# line_sensor.net
KiCad netlist of a schematic drawn in EAGLE
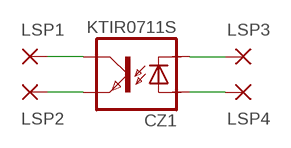
[diagram p0: schematic, sheet 1]

(export (version "E")
  (design (tool "Eeschema 10.0.6"))
  (components
    (comp (ref "CZ1")
      (value "KTIR0711S")
      (footprint "eagle-import:TOP")
      (libsource (lib "eagle-import") (part "KTIR0711S"))
    )
    (comp (ref "LSP1")
      (value "1,6/0,9")
      (footprint "eagle-import:1,6_0,9")
      (libsource (lib "eagle-import") (part "1,6/0,9"))
    )
    (comp (ref "LSP2")
      (value "1,6/0,9")
      (footprint "eagle-import:1,6_0,9")
      (libsource (lib "eagle-import") (part "1,6/0,9"))
    )
    (comp (ref "LSP3")
      (value "1,6/0,9")
      (footprint "eagle-import:1,6_0,9")
      (libsource (lib "eagle-import") (part "1,6/0,9"))
    )
    (comp (ref "LSP4")
      (value "1,6/0,9")
      (footprint "eagle-import:1,6_0,9")
      (libsource (lib "eagle-import") (part "1,6/0,9"))
    )
  )
  (nets
    (net (code "1") (name "Net-(LSP1-P)") (class "Default")
      (node (ref "CZ1") (pin "KOLEKTOR") (pinfunction "KOLEKTOR_KOLEKTOR") (pintype "bidirectional"))
      (node (ref "LSP1") (pin "1") (pinfunction "P_1") (pintype "passive"))
    )
    (net (code "2") (name "Net-(LSP2-P)") (class "Default")
      (node (ref "CZ1") (pin "EMITER") (pinfunction "EMITER_EMITER") (pintype "bidirectional"))
      (node (ref "LSP2") (pin "1") (pinfunction "P_1") (pintype "passive"))
    )
    (net (code "3") (name "Net-(LSP3-P)") (class "Default")
      (node (ref "CZ1") (pin "KATODA") (pinfunction "KATODA_KATODA") (pintype "passive"))
      (node (ref "LSP3") (pin "1") (pinfunction "P_1") (pintype "passive"))
    )
    (net (code "4") (name "Net-(LSP4-P)") (class "Default")
      (node (ref "CZ1") (pin "ANODA") (pinfunction "ANODA_ANODA") (pintype "passive"))
      (node (ref "LSP4") (pin "1") (pinfunction "P_1") (pintype "passive"))
    )
  )
)
